# GECBalloonMCUFlightBoard_REV2_0_5-6-19.net
KiCad netlist of a schematic drawn in EAGLE
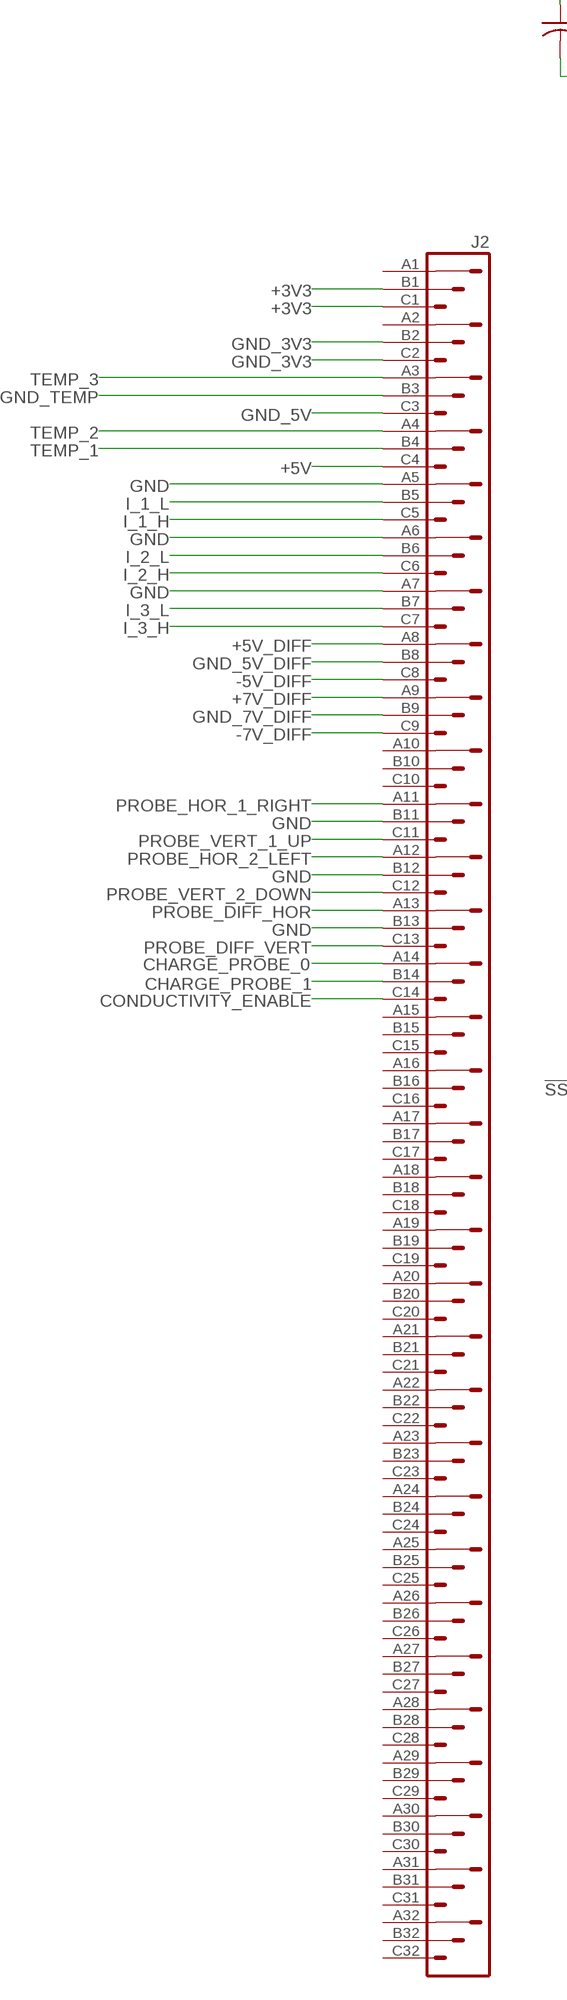
[diagram p0: schematic, sheet 1, part 1 of 2]
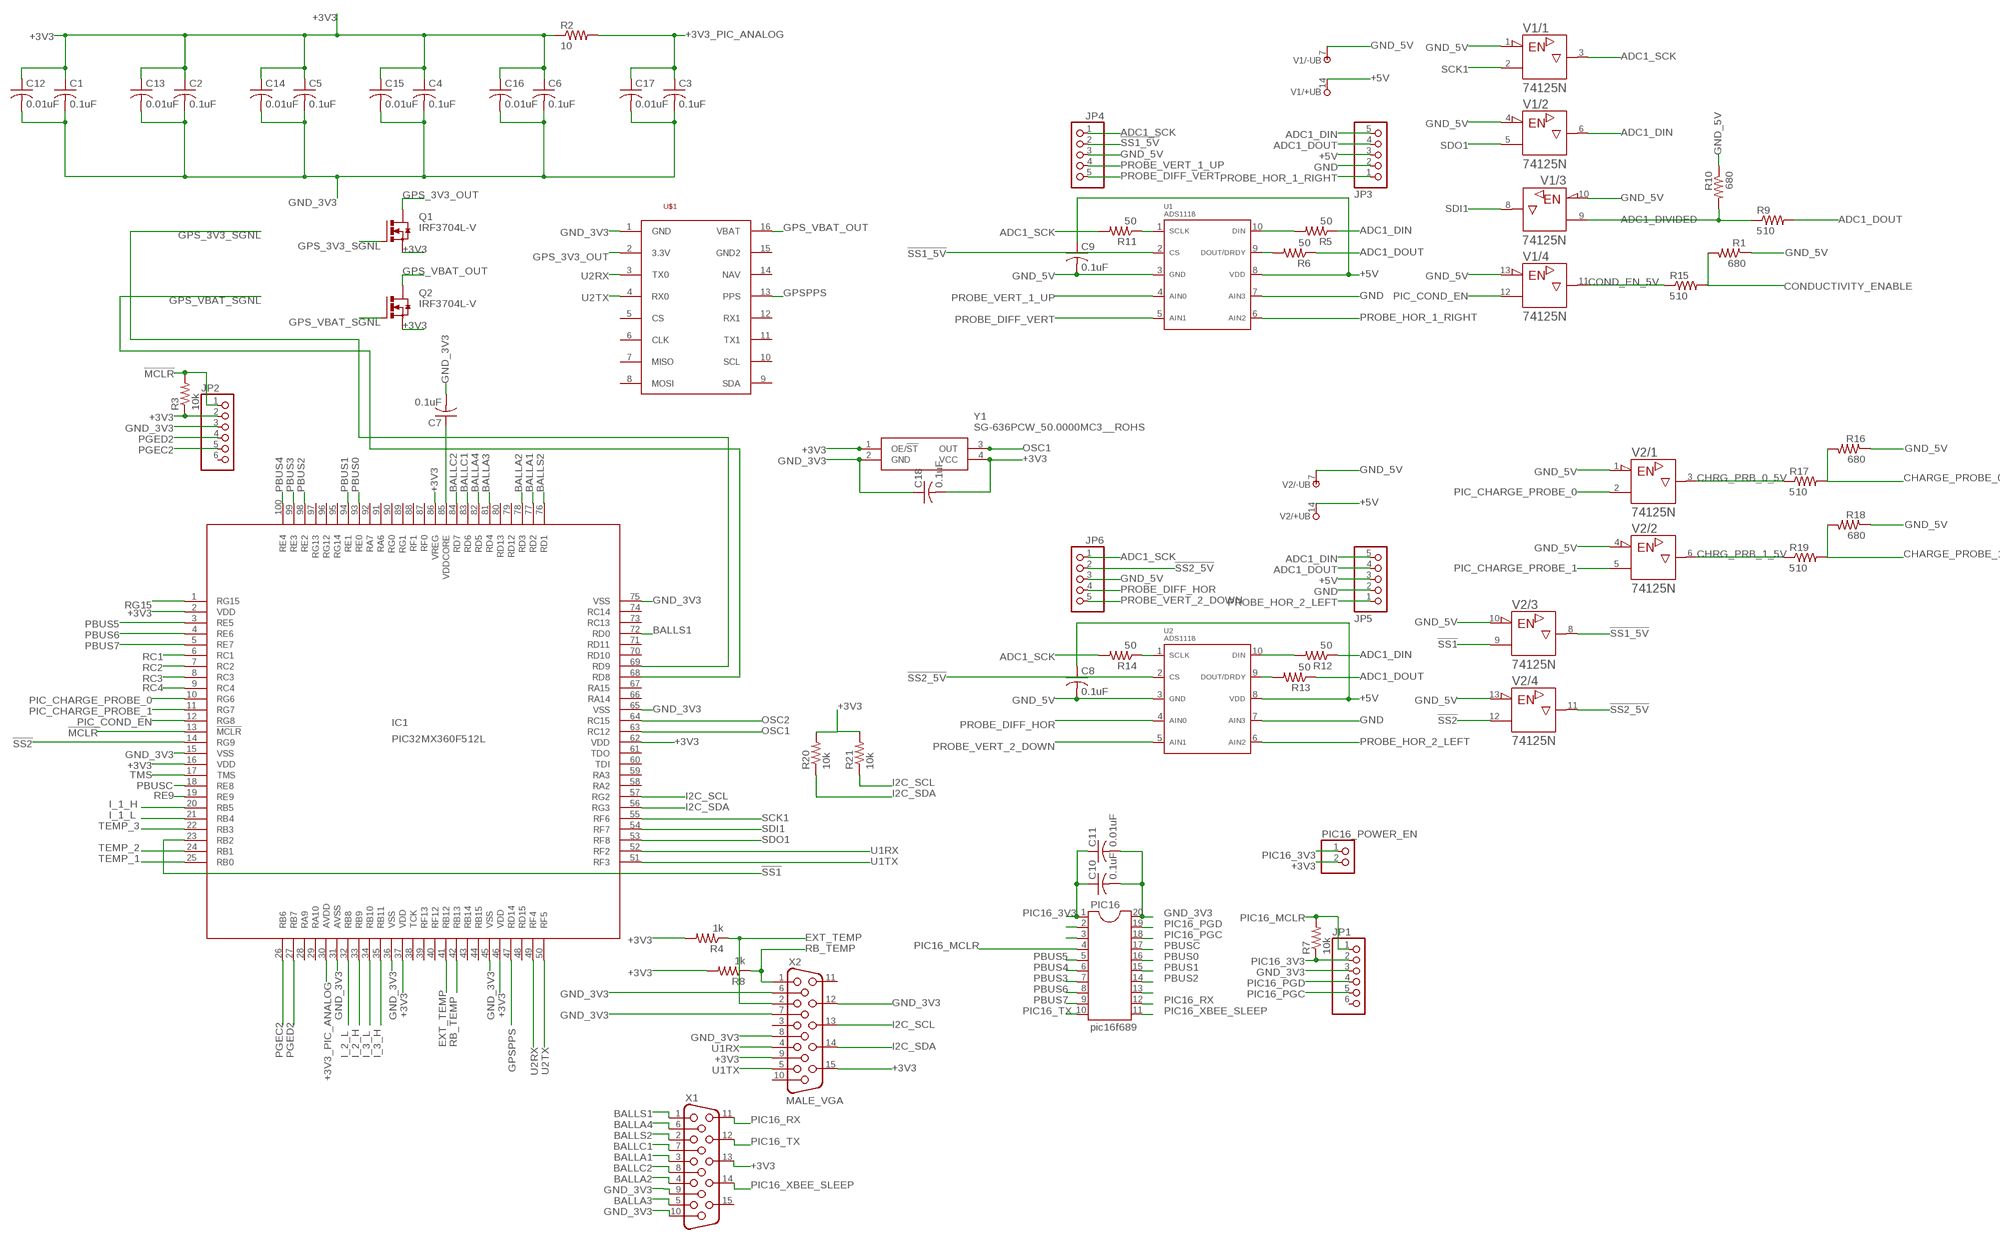
[diagram p1: schematic, sheet 1, part 2 of 2]

(export (version "E")
  (design (tool "Eeschema 10.0.6"))
  (components
    (comp (ref "C1")
      (value "0.1uF")
      (footprint "eagle-import:C1206")
      (libsource (lib "eagle-import") (part "C-USC1206"))
    )
    (comp (ref "C2")
      (value "0.1uF")
      (footprint "eagle-import:C1206")
      (libsource (lib "eagle-import") (part "C-USC1206"))
    )
    (comp (ref "C3")
      (value "0.1uF")
      (footprint "eagle-import:C1206")
      (libsource (lib "eagle-import") (part "C-USC1206"))
    )
    (comp (ref "C4")
      (value "0.1uF")
      (footprint "eagle-import:C1206")
      (libsource (lib "eagle-import") (part "C-USC1206"))
    )
    (comp (ref "C5")
      (value "0.1uF")
      (footprint "eagle-import:C1206")
      (libsource (lib "eagle-import") (part "C-USC1206"))
    )
    (comp (ref "C6")
      (value "0.1uF")
      (footprint "eagle-import:C1206")
      (libsource (lib "eagle-import") (part "C-USC1206"))
    )
    (comp (ref "C7")
      (value "0.1uF")
      (footprint "eagle-import:C1206")
      (libsource (lib "eagle-import") (part "C-USC1206"))
    )
    (comp (ref "C8")
      (value "0.1uF")
      (footprint "eagle-import:C1206")
      (libsource (lib "eagle-import") (part "C-USC1206"))
    )
    (comp (ref "C9")
      (value "0.1uF")
      (footprint "eagle-import:C1206")
      (libsource (lib "eagle-import") (part "C-USC1206"))
    )
    (comp (ref "C10")
      (value "0.1uF")
      (footprint "eagle-import:C1206")
      (libsource (lib "eagle-import") (part "C-USC1206"))
    )
    (comp (ref "C11")
      (value "0.01uF")
      (footprint "eagle-import:C1206")
      (libsource (lib "eagle-import") (part "C-USC1206"))
    )
    (comp (ref "C12")
      (value "0.01uF")
      (footprint "eagle-import:C1206")
      (libsource (lib "eagle-import") (part "C-USC1206"))
    )
    (comp (ref "C13")
      (value "0.01uF")
      (footprint "eagle-import:C1206")
      (libsource (lib "eagle-import") (part "C-USC1206"))
    )
    (comp (ref "C14")
      (value "0.01uF")
      (footprint "eagle-import:C1206")
      (libsource (lib "eagle-import") (part "C-USC1206"))
    )
    (comp (ref "C15")
      (value "0.01uF")
      (footprint "eagle-import:C1206")
      (libsource (lib "eagle-import") (part "C-USC1206"))
    )
    (comp (ref "C16")
      (value "0.01uF")
      (footprint "eagle-import:C1206")
      (libsource (lib "eagle-import") (part "C-USC1206"))
    )
    (comp (ref "C17")
      (value "0.01uF")
      (footprint "eagle-import:C1206")
      (libsource (lib "eagle-import") (part "C-USC1206"))
    )
    (comp (ref "C18")
      (value "0.1uF")
      (footprint "eagle-import:C1206")
      (libsource (lib "eagle-import") (part "C-USC1206"))
    )
    (comp (ref "IC1")
      (value "PIC32MX360F512L")
      (footprint "eagle-import:TQFP100")
      (libsource (lib "eagle-import") (part "PIC32MX360F512L"))
    )
    (comp (ref "J2")
      (value "VG96KB")
      (footprint "eagle-import:VG96KB")
      (libsource (lib "eagle-import") (part "VG96KB"))
    )
    (comp (ref "JP1")
      (value "PINHD-1X6")
      (footprint "eagle-import:1X06")
      (libsource (lib "eagle-import") (part "PINHD-1X6"))
    )
    (comp (ref "JP2")
      (value "PINHD-1X6")
      (footprint "eagle-import:1X06")
      (libsource (lib "eagle-import") (part "PINHD-1X6"))
    )
    (comp (ref "JP3")
      (value "PINHD-1X5")
      (footprint "eagle-import:1X05")
      (libsource (lib "eagle-import") (part "PINHD-1X5"))
    )
    (comp (ref "JP4")
      (value "PINHD-1X5")
      (footprint "eagle-import:1X05")
      (libsource (lib "eagle-import") (part "PINHD-1X5"))
    )
    (comp (ref "JP5")
      (value "PINHD-1X5")
      (footprint "eagle-import:1X05")
      (libsource (lib "eagle-import") (part "PINHD-1X5"))
    )
    (comp (ref "JP6")
      (value "PINHD-1X5")
      (footprint "eagle-import:1X05")
      (libsource (lib "eagle-import") (part "PINHD-1X5"))
    )
    (comp (ref "PIC16")
      (value "pic16f689")
      (footprint "eagle-import:DIL20")
      (libsource (lib "eagle-import") (part "DIL20"))
    )
    (comp (ref "PIC16_POWER_EN")
      (value "PINHD-1X2")
      (footprint "eagle-import:1X02")
      (libsource (lib "eagle-import") (part "PINHD-1X2"))
    )
    (comp (ref "Q1")
      (value "IRF3704L-V")
      (footprint "eagle-import:TO262-V")
      (libsource (lib "eagle-import") (part "IRF3704L-V"))
    )
    (comp (ref "Q2")
      (value "IRF3704L-V")
      (footprint "eagle-import:TO262-V")
      (libsource (lib "eagle-import") (part "IRF3704L-V"))
    )
    (comp (ref "R1")
      (value "680")
      (footprint "eagle-import:R1206")
      (libsource (lib "eagle-import") (part "resistor_R-US_R1206"))
    )
    (comp (ref "R2")
      (value "10")
      (footprint "eagle-import:M1206")
      (libsource (lib "eagle-import") (part "R-US_M1206"))
    )
    (comp (ref "R3")
      (value "10k")
      (footprint "eagle-import:M1206")
      (libsource (lib "eagle-import") (part "R-US_M1206"))
    )
    (comp (ref "R4")
      (value "1k")
      (footprint "eagle-import:0414_15")
      (libsource (lib "eagle-import") (part "resistor_R-US_0414/15"))
    )
    (comp (ref "R5")
      (value "50")
      (footprint "eagle-import:M1206")
      (libsource (lib "eagle-import") (part "R-US_M1206"))
    )
    (comp (ref "R6")
      (value "50")
      (footprint "eagle-import:M1206")
      (libsource (lib "eagle-import") (part "R-US_M1206"))
    )
    (comp (ref "R7")
      (value "10k")
      (footprint "eagle-import:M1206")
      (libsource (lib "eagle-import") (part "R-US_M1206"))
    )
    (comp (ref "R8")
      (value "1k")
      (footprint "eagle-import:0414_15")
      (libsource (lib "eagle-import") (part "resistor_R-US_0414/15"))
    )
    (comp (ref "R9")
      (value "510")
      (footprint "eagle-import:R1206")
      (libsource (lib "eagle-import") (part "resistor_R-US_R1206"))
    )
    (comp (ref "R10")
      (value "680")
      (footprint "eagle-import:R1206")
      (libsource (lib "eagle-import") (part "resistor_R-US_R1206"))
    )
    (comp (ref "R11")
      (value "50")
      (footprint "eagle-import:M1206")
      (libsource (lib "eagle-import") (part "R-US_M1206"))
    )
    (comp (ref "R12")
      (value "50")
      (footprint "eagle-import:M1206")
      (libsource (lib "eagle-import") (part "R-US_M1206"))
    )
    (comp (ref "R13")
      (value "50")
      (footprint "eagle-import:M1206")
      (libsource (lib "eagle-import") (part "R-US_M1206"))
    )
    (comp (ref "R14")
      (value "50")
      (footprint "eagle-import:M1206")
      (libsource (lib "eagle-import") (part "R-US_M1206"))
    )
    (comp (ref "R15")
      (value "510")
      (footprint "eagle-import:R1206")
      (libsource (lib "eagle-import") (part "resistor_R-US_R1206"))
    )
    (comp (ref "R16")
      (value "680")
      (footprint "eagle-import:R1206")
      (libsource (lib "eagle-import") (part "resistor_R-US_R1206"))
    )
    (comp (ref "R17")
      (value "510")
      (footprint "eagle-import:R1206")
      (libsource (lib "eagle-import") (part "resistor_R-US_R1206"))
    )
    (comp (ref "R18")
      (value "680")
      (footprint "eagle-import:R1206")
      (libsource (lib "eagle-import") (part "resistor_R-US_R1206"))
    )
    (comp (ref "R19")
      (value "510")
      (footprint "eagle-import:R1206")
      (libsource (lib "eagle-import") (part "resistor_R-US_R1206"))
    )
    (comp (ref "R20")
      (value "10k")
      (footprint "eagle-import:M1206")
      (libsource (lib "eagle-import") (part "R-US_M1206"))
    )
    (comp (ref "R21")
      (value "10k")
      (footprint "eagle-import:M1206")
      (libsource (lib "eagle-import") (part "R-US_M1206"))
    )
    (comp (ref "U$1")
      (value "SPARKFUN_VENUS_GPS_BREAKOUT")
      (footprint "eagle-import:SPARKFUN_BOARD")
      (libsource (lib "eagle-import") (part "SPARKFUN_VENUS_GPS_BREAKOUT"))
    )
    (comp (ref "U1")
      (value "ADS1118")
      (footprint "eagle-import:MSOP10")
      (libsource (lib "eagle-import") (part "ADS1118_MSOP10"))
    )
    (comp (ref "U2")
      (value "ADS1118")
      (footprint "eagle-import:MSOP10")
      (libsource (lib "eagle-import") (part "ADS1118_MSOP10"))
    )
    (comp (ref "V1")
      (value "74125N")
      (footprint "eagle-import:DIL14")
      (libsource (lib "eagle-import") (part "74125N"))
    )
    (comp (ref "V2")
      (value "74125N")
      (footprint "eagle-import:DIL14")
      (libsource (lib "eagle-import") (part "74125N"))
    )
    (comp (ref "X1")
      (value "HF15H")
      (footprint "eagle-import:HDF15H")
      (libsource (lib "eagle-import") (part "HF15H"))
    )
    (comp (ref "X2")
      (value "MALE_VGA")
      (footprint "eagle-import:MALE_PACKAGE")
      (libsource (lib "eagle-import") (part "MALE_VGA"))
    )
    (comp (ref "Y1")
      (value "SG-636PCW_50.0000MC3__ROHS")
      (footprint "eagle-import:SG-636")
      (fields (field (name "ARROW_PART_NUMBER") "SG-636PCW 50.0000MC3: ROHS"))
      (libsource (lib "eagle-import") (part "SG-636PCW_50.0000MC3__ROHS"))
    )
  )
  (nets
    (net (code "1") (name "/+3V3") (class "Default")
      (node (ref "C1") (pin "1") (pinfunction "1_1") (pintype "passive"))
      (node (ref "C12") (pin "1") (pinfunction "1_1") (pintype "passive"))
      (node (ref "C13") (pin "1") (pinfunction "1_1") (pintype "passive"))
      (node (ref "C14") (pin "1") (pinfunction "1_1") (pintype "passive"))
      (node (ref "C15") (pin "1") (pinfunction "1_1") (pintype "passive"))
      (node (ref "C16") (pin "1") (pinfunction "1_1") (pintype "passive"))
      (node (ref "C18") (pin "2") (pinfunction "2_2") (pintype "passive"))
      (node (ref "C2") (pin "1") (pinfunction "1_1") (pintype "passive"))
      (node (ref "C4") (pin "1") (pinfunction "1_1") (pintype "passive"))
      (node (ref "C5") (pin "1") (pinfunction "1_1") (pintype "passive"))
      (node (ref "C6") (pin "1") (pinfunction "1_1") (pintype "passive"))
      (node (ref "IC1") (pin "16") (pinfunction "VDD_16") (pintype "power_in"))
      (node (ref "IC1") (pin "2") (pinfunction "VDD_2") (pintype "power_in"))
      (node (ref "IC1") (pin "37") (pinfunction "VDD_37") (pintype "power_in"))
      (node (ref "IC1") (pin "46") (pinfunction "VDD_46") (pintype "power_in"))
      (node (ref "IC1") (pin "62") (pinfunction "VDD_62") (pintype "power_in"))
      (node (ref "IC1") (pin "86") (pinfunction "VREG_86") (pintype "passive"))
      (node (ref "J2") (pin "B1") (pinfunction "B1_B1") (pintype "passive"))
      (node (ref "J2") (pin "C1") (pinfunction "C1_C1") (pintype "passive"))
      (node (ref "JP2") (pin "2") (pinfunction "2_2") (pintype "passive"))
      (node (ref "PIC16_POWER_EN") (pin "2") (pinfunction "2_2") (pintype "passive"))
      (node (ref "Q1") (pin "3") (pinfunction "S_3") (pintype "passive"))
      (node (ref "Q2") (pin "3") (pinfunction "S_3") (pintype "passive"))
      (node (ref "R2") (pin "1") (pinfunction "1_1") (pintype "passive"))
      (node (ref "R20") (pin "2") (pinfunction "2_2") (pintype "passive"))
      (node (ref "R21") (pin "2") (pinfunction "2_2") (pintype "passive"))
      (node (ref "R3") (pin "1") (pinfunction "1_1") (pintype "passive"))
      (node (ref "R4") (pin "2") (pinfunction "2_2") (pintype "passive"))
      (node (ref "R8") (pin "2") (pinfunction "2_2") (pintype "passive"))
      (node (ref "X1") (pin "13") (pinfunction "13_13") (pintype "passive"))
      (node (ref "X2") (pin "15") (pinfunction "15_15") (pintype "passive"))
      (node (ref "X2") (pin "9") (pinfunction "9_9") (pintype "passive"))
      (node (ref "Y1") (pin "1") (pinfunction "OE/~{ST}_1") (pintype "input"))
      (node (ref "Y1") (pin "4") (pinfunction "VCC_4") (pintype "power_in"))
    )
    (net (code "2") (name "/+3V3_PIC_ANALOG") (class "Default")
      (node (ref "C17") (pin "1") (pinfunction "1_1") (pintype "passive"))
      (node (ref "C3") (pin "1") (pinfunction "1_1") (pintype "passive"))
      (node (ref "IC1") (pin "30") (pinfunction "AVDD_30") (pintype "power_in"))
      (node (ref "R2") (pin "2") (pinfunction "2_2") (pintype "passive"))
    )
    (net (code "3") (name "/+5V") (class "Default")
      (node (ref "C8") (pin "1") (pinfunction "1_1") (pintype "passive"))
      (node (ref "C9") (pin "1") (pinfunction "1_1") (pintype "passive"))
      (node (ref "J2") (pin "C4") (pinfunction "C4_C4") (pintype "passive"))
      (node (ref "JP3") (pin "3") (pinfunction "3_3") (pintype "passive"))
      (node (ref "JP5") (pin "3") (pinfunction "3_3") (pintype "passive"))
      (node (ref "U1") (pin "8") (pinfunction "VDD_8") (pintype "bidirectional"))
      (node (ref "U2") (pin "8") (pinfunction "VDD_8") (pintype "bidirectional"))
      (node (ref "V1") (pin "14") (pinfunction "+UB_14") (pintype "power_in"))
      (node (ref "V2") (pin "14") (pinfunction "+UB_14") (pintype "power_in"))
    )
    (net (code "4") (name "/+5V_DIFF") (class "Default")
      (node (ref "J2") (pin "A8") (pinfunction "A8_A8") (pintype "passive"))
    )
    (net (code "5") (name "/+7V_DIFF") (class "Default")
      (node (ref "J2") (pin "A9") (pinfunction "A9_A9") (pintype "passive"))
    )
    (net (code "6") (name "/-5V_DIFF") (class "Default")
      (node (ref "J2") (pin "C8") (pinfunction "C8_C8") (pintype "passive"))
    )
    (net (code "7") (name "/-7V_DIFF") (class "Default")
      (node (ref "J2") (pin "C9") (pinfunction "C9_C9") (pintype "passive"))
    )
    (net (code "8") (name "/ADC1_DIN") (class "Default")
      (node (ref "JP3") (pin "5") (pinfunction "5_5") (pintype "passive"))
      (node (ref "JP5") (pin "5") (pinfunction "5_5") (pintype "passive"))
      (node (ref "R12") (pin "1") (pinfunction "1_1") (pintype "passive"))
      (node (ref "R5") (pin "1") (pinfunction "1_1") (pintype "passive"))
      (node (ref "V1") (pin "6") (pinfunction "Y_6") (pintype "tri_state"))
    )
    (net (code "9") (name "/ADC1_DIVIDED") (class "Default")
      (node (ref "R10") (pin "2") (pinfunction "2_2") (pintype "passive"))
      (node (ref "R9") (pin "1") (pinfunction "1_1") (pintype "passive"))
      (node (ref "V1") (pin "9") (pinfunction "A_9") (pintype "input"))
    )
    (net (code "10") (name "/ADC1_DOUT") (class "Default")
      (node (ref "JP3") (pin "4") (pinfunction "4_4") (pintype "passive"))
      (node (ref "JP5") (pin "4") (pinfunction "4_4") (pintype "passive"))
      (node (ref "R13") (pin "1") (pinfunction "1_1") (pintype "passive"))
      (node (ref "R6") (pin "1") (pinfunction "1_1") (pintype "passive"))
      (node (ref "R9") (pin "2") (pinfunction "2_2") (pintype "passive"))
    )
    (net (code "11") (name "/ADC1_SCK") (class "Default")
      (node (ref "JP4") (pin "1") (pinfunction "1_1") (pintype "passive"))
      (node (ref "JP6") (pin "1") (pinfunction "1_1") (pintype "passive"))
      (node (ref "R11") (pin "2") (pinfunction "2_2") (pintype "passive"))
      (node (ref "R14") (pin "2") (pinfunction "2_2") (pintype "passive"))
      (node (ref "V1") (pin "3") (pinfunction "Y_3") (pintype "tri_state"))
    )
    (net (code "12") (name "/BALLA1") (class "Default")
      (node (ref "IC1") (pin "77") (pinfunction "RD2_77") (pintype "bidirectional"))
      (node (ref "X1") (pin "3") (pinfunction "3_3") (pintype "passive"))
    )
    (net (code "13") (name "/BALLA2") (class "Default")
      (node (ref "IC1") (pin "78") (pinfunction "RD3_78") (pintype "bidirectional"))
      (node (ref "X1") (pin "4") (pinfunction "4_4") (pintype "passive"))
    )
    (net (code "14") (name "/BALLA3") (class "Default")
      (node (ref "IC1") (pin "81") (pinfunction "RD4_81") (pintype "bidirectional"))
      (node (ref "X1") (pin "5") (pinfunction "5_5") (pintype "passive"))
    )
    (net (code "15") (name "/BALLA4") (class "Default")
      (node (ref "IC1") (pin "82") (pinfunction "RD5_82") (pintype "bidirectional"))
      (node (ref "X1") (pin "6") (pinfunction "6_6") (pintype "passive"))
    )
    (net (code "16") (name "/BALLC1") (class "Default")
      (node (ref "IC1") (pin "83") (pinfunction "RD6_83") (pintype "bidirectional"))
      (node (ref "X1") (pin "7") (pinfunction "7_7") (pintype "passive"))
    )
    (net (code "17") (name "/BALLC2") (class "Default")
      (node (ref "IC1") (pin "84") (pinfunction "RD7_84") (pintype "bidirectional"))
      (node (ref "X1") (pin "8") (pinfunction "8_8") (pintype "passive"))
    )
    (net (code "18") (name "/BALLS1") (class "Default")
      (node (ref "IC1") (pin "72") (pinfunction "RD0_72") (pintype "bidirectional"))
      (node (ref "X1") (pin "1") (pinfunction "1_1") (pintype "passive"))
    )
    (net (code "19") (name "/BALLS2") (class "Default")
      (node (ref "IC1") (pin "76") (pinfunction "RD1_76") (pintype "bidirectional"))
      (node (ref "X1") (pin "2") (pinfunction "2_2") (pintype "passive"))
    )
    (net (code "20") (name "/CHARGE_PROBE_0") (class "Default")
      (node (ref "J2") (pin "A14") (pinfunction "A14_A14") (pintype "passive"))
      (node (ref "R16") (pin "2") (pinfunction "2_2") (pintype "passive"))
      (node (ref "R17") (pin "2") (pinfunction "2_2") (pintype "passive"))
    )
    (net (code "21") (name "/CHARGE_PROBE_1") (class "Default")
      (node (ref "J2") (pin "B14") (pinfunction "B14_B14") (pintype "passive"))
      (node (ref "R18") (pin "2") (pinfunction "2_2") (pintype "passive"))
      (node (ref "R19") (pin "2") (pinfunction "2_2") (pintype "passive"))
    )
    (net (code "22") (name "/CHRG_PRB_0_5V") (class "Default")
      (node (ref "R17") (pin "1") (pinfunction "1_1") (pintype "passive"))
      (node (ref "V2") (pin "3") (pinfunction "Y_3") (pintype "tri_state"))
    )
    (net (code "23") (name "/CHRG_PRB_1_5V") (class "Default")
      (node (ref "R19") (pin "1") (pinfunction "1_1") (pintype "passive"))
      (node (ref "V2") (pin "6") (pinfunction "Y_6") (pintype "tri_state"))
    )
    (net (code "24") (name "/CONDUCTIVITY_ENABLE") (class "Default")
      (node (ref "J2") (pin "C14") (pinfunction "C14_C14") (pintype "passive"))
      (node (ref "R1") (pin "2") (pinfunction "2_2") (pintype "passive"))
      (node (ref "R15") (pin "2") (pinfunction "2_2") (pintype "passive"))
    )
    (net (code "25") (name "/COND_EN_5V") (class "Default")
      (node (ref "R15") (pin "1") (pinfunction "1_1") (pintype "passive"))
      (node (ref "V1") (pin "11") (pinfunction "Y_11") (pintype "tri_state"))
    )
    (net (code "26") (name "/EXT_TEMP") (class "Default")
      (node (ref "IC1") (pin "41") (pinfunction "RB12_41") (pintype "bidirectional"))
      (node (ref "R4") (pin "1") (pinfunction "1_1") (pintype "passive"))
      (node (ref "X2") (pin "2") (pinfunction "2_2") (pintype "passive"))
    )
    (net (code "27") (name "/GND") (class "Default")
      (node (ref "J2") (pin "A5") (pinfunction "A5_A5") (pintype "passive"))
      (node (ref "J2") (pin "A6") (pinfunction "A6_A6") (pintype "passive"))
      (node (ref "J2") (pin "A7") (pinfunction "A7_A7") (pintype "passive"))
      (node (ref "J2") (pin "B11") (pinfunction "B11_B11") (pintype "passive"))
      (node (ref "J2") (pin "B12") (pinfunction "B12_B12") (pintype "passive"))
      (node (ref "J2") (pin "B13") (pinfunction "B13_B13") (pintype "passive"))
      (node (ref "JP3") (pin "2") (pinfunction "2_2") (pintype "passive"))
      (node (ref "JP5") (pin "2") (pinfunction "2_2") (pintype "passive"))
      (node (ref "U1") (pin "7") (pinfunction "AIN3_7") (pintype "bidirectional"))
      (node (ref "U2") (pin "7") (pinfunction "AIN3_7") (pintype "bidirectional"))
    )
    (net (code "28") (name "/GND_3V3") (class "Default")
      (node (ref "C1") (pin "2") (pinfunction "2_2") (pintype "passive"))
      (node (ref "C10") (pin "2") (pinfunction "2_2") (pintype "passive"))
      (node (ref "C11") (pin "2") (pinfunction "2_2") (pintype "passive"))
      (node (ref "C12") (pin "2") (pinfunction "2_2") (pintype "passive"))
      (node (ref "C13") (pin "2") (pinfunction "2_2") (pintype "passive"))
      (node (ref "C14") (pin "2") (pinfunction "2_2") (pintype "passive"))
      (node (ref "C15") (pin "2") (pinfunction "2_2") (pintype "passive"))
      (node (ref "C16") (pin "2") (pinfunction "2_2") (pintype "passive"))
      (node (ref "C17") (pin "2") (pinfunction "2_2") (pintype "passive"))
      (node (ref "C18") (pin "1") (pinfunction "1_1") (pintype "passive"))
      (node (ref "C2") (pin "2") (pinfunction "2_2") (pintype "passive"))
      (node (ref "C3") (pin "2") (pinfunction "2_2") (pintype "passive"))
      (node (ref "C4") (pin "2") (pinfunction "2_2") (pintype "passive"))
      (node (ref "C5") (pin "2") (pinfunction "2_2") (pintype "passive"))
      (node (ref "C6") (pin "2") (pinfunction "2_2") (pintype "passive"))
      (node (ref "C7") (pin "2") (pinfunction "2_2") (pintype "passive"))
      (node (ref "IC1") (pin "15") (pinfunction "VSS_15") (pintype "power_in"))
      (node (ref "IC1") (pin "31") (pinfunction "AVSS_31") (pintype "power_in"))
      (node (ref "IC1") (pin "36") (pinfunction "VSS_36") (pintype "power_in"))
      (node (ref "IC1") (pin "45") (pinfunction "VSS_45") (pintype "power_in"))
      (node (ref "IC1") (pin "65") (pinfunction "VSS_65") (pintype "power_in"))
      (node (ref "IC1") (pin "75") (pinfunction "VSS_75") (pintype "power_in"))
      (node (ref "J2") (pin "B2") (pinfunction "B2_B2") (pintype "passive"))
      (node (ref "J2") (pin "C2") (pinfunction "C2_C2") (pintype "passive"))
      (node (ref "JP1") (pin "3") (pinfunction "3_3") (pintype "passive"))
      (node (ref "JP2") (pin "3") (pinfunction "3_3") (pintype "passive"))
      (node (ref "PIC16") (pin "20") (pinfunction "20_20") (pintype "passive"))
      (node (ref "U$1") (pin "1") (pinfunction "GND_1") (pintype "bidirectional"))
      (node (ref "X1") (pin "10") (pinfunction "10_10") (pintype "passive"))
      (node (ref "X1") (pin "9") (pinfunction "9_9") (pintype "passive"))
      (node (ref "X2") (pin "12") (pinfunction "12_12") (pintype "passive"))
      (node (ref "X2") (pin "6") (pinfunction "6_6") (pintype "passive"))
      (node (ref "X2") (pin "7") (pinfunction "7_7") (pintype "passive"))
      (node (ref "X2") (pin "8") (pinfunction "8_8") (pintype "passive"))
      (node (ref "Y1") (pin "2") (pinfunction "GND_2") (pintype "power_in"))
    )
    (net (code "29") (name "/GND_5V") (class "Default")
      (node (ref "C8") (pin "2") (pinfunction "2_2") (pintype "passive"))
      (node (ref "C9") (pin "2") (pinfunction "2_2") (pintype "passive"))
      (node (ref "J2") (pin "C3") (pinfunction "C3_C3") (pintype "passive"))
      (node (ref "JP4") (pin "3") (pinfunction "3_3") (pintype "passive"))
      (node (ref "JP6") (pin "3") (pinfunction "3_3") (pintype "passive"))
      (node (ref "R1") (pin "1") (pinfunction "1_1") (pintype "passive"))
      (node (ref "R10") (pin "1") (pinfunction "1_1") (pintype "passive"))
      (node (ref "R16") (pin "1") (pinfunction "1_1") (pintype "passive"))
      (node (ref "R18") (pin "1") (pinfunction "1_1") (pintype "passive"))
      (node (ref "U1") (pin "3") (pinfunction "GND_3") (pintype "bidirectional"))
      (node (ref "U2") (pin "3") (pinfunction "GND_3") (pintype "bidirectional"))
      (node (ref "V1") (pin "1") (pinfunction "~{G}_1") (pintype "input"))
      (node (ref "V1") (pin "10") (pinfunction "~{G}_10") (pintype "input"))
      (node (ref "V1") (pin "13") (pinfunction "~{G}_13") (pintype "input"))
      (node (ref "V1") (pin "4") (pinfunction "~{G}_4") (pintype "input"))
      (node (ref "V1") (pin "7") (pinfunction "-UB_7") (pintype "power_in"))
      (node (ref "V2") (pin "1") (pinfunction "~{G}_1") (pintype "input"))
      (node (ref "V2") (pin "10") (pinfunction "~{G}_10") (pintype "input"))
      (node (ref "V2") (pin "13") (pinfunction "~{G}_13") (pintype "input"))
      (node (ref "V2") (pin "4") (pinfunction "~{G}_4") (pintype "input"))
      (node (ref "V2") (pin "7") (pinfunction "-UB_7") (pintype "power_in"))
    )
    (net (code "30") (name "/GND_5V_DIFF") (class "Default")
      (node (ref "J2") (pin "B8") (pinfunction "B8_B8") (pintype "passive"))
    )
    (net (code "31") (name "/GND_7V_DIFF") (class "Default")
      (node (ref "J2") (pin "B9") (pinfunction "B9_B9") (pintype "passive"))
    )
    (net (code "32") (name "/GND_TEMP") (class "Default")
      (node (ref "J2") (pin "B3") (pinfunction "B3_B3") (pintype "passive"))
    )
    (net (code "33") (name "/GPSPPS") (class "Default")
      (node (ref "IC1") (pin "47") (pinfunction "RD14_47") (pintype "bidirectional"))
      (node (ref "U$1") (pin "13") (pinfunction "PPS_13") (pintype "bidirectional"))
    )
    (net (code "34") (name "/GPS_3V3_OUT") (class "Default")
      (node (ref "Q1") (pin "2") (pinfunction "D_2") (pintype "passive"))
      (node (ref "U$1") (pin "2") (pinfunction "3.3V_2") (pintype "bidirectional"))
    )
    (net (code "35") (name "/GPS_3V3_SGNL") (class "Default")
      (node (ref "IC1") (pin "69") (pinfunction "RD9_69") (pintype "bidirectional"))
      (node (ref "Q1") (pin "1") (pinfunction "G_1") (pintype "passive"))
    )
    (net (code "36") (name "/GPS_VBAT_OUT") (class "Default")
      (node (ref "Q2") (pin "2") (pinfunction "D_2") (pintype "passive"))
      (node (ref "U$1") (pin "16") (pinfunction "VBAT_16") (pintype "bidirectional"))
    )
    (net (code "37") (name "/GPS_VBAT_SGNL") (class "Default")
      (node (ref "IC1") (pin "68") (pinfunction "RD8_68") (pintype "bidirectional"))
      (node (ref "Q2") (pin "1") (pinfunction "G_1") (pintype "passive"))
    )
    (net (code "38") (name "/I2C_SCL") (class "Default")
      (node (ref "IC1") (pin "57") (pinfunction "RG2_57") (pintype "bidirectional"))
      (node (ref "R21") (pin "1") (pinfunction "1_1") (pintype "passive"))
      (node (ref "X2") (pin "13") (pinfunction "13_13") (pintype "passive"))
    )
    (net (code "39") (name "/I2C_SDA") (class "Default")
      (node (ref "IC1") (pin "56") (pinfunction "RG3_56") (pintype "bidirectional"))
      (node (ref "R20") (pin "1") (pinfunction "1_1") (pintype "passive"))
      (node (ref "X2") (pin "14") (pinfunction "14_14") (pintype "passive"))
    )
    (net (code "40") (name "/I_1_H") (class "Default")
      (node (ref "IC1") (pin "20") (pinfunction "RB5_20") (pintype "bidirectional"))
      (node (ref "J2") (pin "C5") (pinfunction "C5_C5") (pintype "passive"))
    )
    (net (code "41") (name "/I_1_L") (class "Default")
      (node (ref "IC1") (pin "21") (pinfunction "RB4_21") (pintype "bidirectional"))
      (node (ref "J2") (pin "B5") (pinfunction "B5_B5") (pintype "passive"))
    )
    (net (code "42") (name "/I_2_H") (class "Default")
      (node (ref "IC1") (pin "33") (pinfunction "RB9_33") (pintype "bidirectional"))
      (node (ref "J2") (pin "C6") (pinfunction "C6_C6") (pintype "passive"))
    )
    (net (code "43") (name "/I_2_L") (class "Default")
      (node (ref "IC1") (pin "32") (pinfunction "RB8_32") (pintype "bidirectional"))
      (node (ref "J2") (pin "B6") (pinfunction "B6_B6") (pintype "passive"))
    )
    (net (code "44") (name "/I_3_H") (class "Default")
      (node (ref "IC1") (pin "35") (pinfunction "RB11_35") (pintype "bidirectional"))
      (node (ref "J2") (pin "C7") (pinfunction "C7_C7") (pintype "passive"))
    )
    (net (code "45") (name "/I_3_L") (class "Default")
      (node (ref "IC1") (pin "34") (pinfunction "RB10_34") (pintype "bidirectional"))
      (node (ref "J2") (pin "B7") (pinfunction "B7_B7") (pintype "passive"))
    )
    (net (code "46") (name "/OSC1") (class "Default")
      (node (ref "IC1") (pin "63") (pinfunction "RC12_63") (pintype "bidirectional"))
      (node (ref "Y1") (pin "3") (pinfunction "OUT_3") (pintype "output"))
    )
    (net (code "47") (name "/OSC2") (class "Default")
      (node (ref "IC1") (pin "64") (pinfunction "RC15_64") (pintype "bidirectional"))
    )
    (net (code "48") (name "/PBUS0") (class "Default")
      (node (ref "IC1") (pin "93") (pinfunction "RE0_93") (pintype "bidirectional"))
      (node (ref "PIC16") (pin "16") (pinfunction "16_16") (pintype "passive"))
    )
    (net (code "49") (name "/PBUS1") (class "Default")
      (node (ref "IC1") (pin "94") (pinfunction "RE1_94") (pintype "bidirectional"))
      (node (ref "PIC16") (pin "15") (pinfunction "15_15") (pintype "passive"))
    )
    (net (code "50") (name "/PBUS2") (class "Default")
      (node (ref "IC1") (pin "98") (pinfunction "RE2_98") (pintype "bidirectional"))
      (node (ref "PIC16") (pin "14") (pinfunction "14_14") (pintype "passive"))
    )
    (net (code "51") (name "/PBUS3") (class "Default")
      (node (ref "IC1") (pin "99") (pinfunction "RE3_99") (pintype "bidirectional"))
      (node (ref "PIC16") (pin "7") (pinfunction "7_7") (pintype "passive"))
    )
    (net (code "52") (name "/PBUS4") (class "Default")
      (node (ref "IC1") (pin "100") (pinfunction "RE4_100") (pintype "bidirectional"))
      (node (ref "PIC16") (pin "6") (pinfunction "6_6") (pintype "passive"))
    )
    (net (code "53") (name "/PBUS5") (class "Default")
      (node (ref "IC1") (pin "3") (pinfunction "RE5_3") (pintype "bidirectional"))
      (node (ref "PIC16") (pin "5") (pinfunction "5_5") (pintype "passive"))
    )
    (net (code "54") (name "/PBUS6") (class "Default")
      (node (ref "IC1") (pin "4") (pinfunction "RE6_4") (pintype "bidirectional"))
      (node (ref "PIC16") (pin "8") (pinfunction "8_8") (pintype "passive"))
    )
    (net (code "55") (name "/PBUS7") (class "Default")
      (node (ref "IC1") (pin "5") (pinfunction "RE7_5") (pintype "bidirectional"))
      (node (ref "PIC16") (pin "9") (pinfunction "9_9") (pintype "passive"))
    )
    (net (code "56") (name "/PBUSC") (class "Default")
      (node (ref "IC1") (pin "18") (pinfunction "RE8_18") (pintype "bidirectional"))
      (node (ref "PIC16") (pin "17") (pinfunction "17_17") (pintype "passive"))
    )
    (net (code "57") (name "/PGEC2") (class "Default")
      (node (ref "IC1") (pin "26") (pinfunction "RB6_26") (pintype "bidirectional"))
      (node (ref "JP2") (pin "5") (pinfunction "5_5") (pintype "passive"))
    )
    (net (code "58") (name "/PGED2") (class "Default")
      (node (ref "IC1") (pin "27") (pinfunction "RB7_27") (pintype "bidirectional"))
      (node (ref "JP2") (pin "4") (pinfunction "4_4") (pintype "passive"))
    )
    (net (code "59") (name "/PIC16_3V3") (class "Default")
      (node (ref "C10") (pin "1") (pinfunction "1_1") (pintype "passive"))
      (node (ref "C11") (pin "1") (pinfunction "1_1") (pintype "passive"))
      (node (ref "JP1") (pin "2") (pinfunction "2_2") (pintype "passive"))
      (node (ref "PIC16") (pin "1") (pinfunction "1_1") (pintype "passive"))
      (node (ref "PIC16_POWER_EN") (pin "1") (pinfunction "1_1") (pintype "passive"))
      (node (ref "R7") (pin "1") (pinfunction "1_1") (pintype "passive"))
    )
    (net (code "60") (name "/PIC16_MCLR") (class "Default")
      (node (ref "JP1") (pin "1") (pinfunction "1_1") (pintype "passive"))
      (node (ref "PIC16") (pin "4") (pinfunction "4_4") (pintype "passive"))
      (node (ref "R7") (pin "2") (pinfunction "2_2") (pintype "passive"))
    )
    (net (code "61") (name "/PIC16_PGC") (class "Default")
      (node (ref "JP1") (pin "5") (pinfunction "5_5") (pintype "passive"))
      (node (ref "PIC16") (pin "18") (pinfunction "18_18") (pintype "passive"))
    )
    (net (code "62") (name "/PIC16_PGD") (class "Default")
      (node (ref "JP1") (pin "4") (pinfunction "4_4") (pintype "passive"))
      (node (ref "PIC16") (pin "19") (pinfunction "19_19") (pintype "passive"))
    )
    (net (code "63") (name "/PIC16_RX") (class "Default")
      (node (ref "PIC16") (pin "12") (pinfunction "12_12") (pintype "passive"))
      (node (ref "X1") (pin "11") (pinfunction "11_11") (pintype "passive"))
    )
    (net (code "64") (name "/PIC16_TX") (class "Default")
      (node (ref "PIC16") (pin "10") (pinfunction "10_10") (pintype "passive"))
      (node (ref "X1") (pin "12") (pinfunction "12_12") (pintype "passive"))
    )
    (net (code "65") (name "/PIC16_XBEE_SLEEP") (class "Default")
      (node (ref "PIC16") (pin "11") (pinfunction "11_11") (pintype "passive"))
      (node (ref "X1") (pin "14") (pinfunction "14_14") (pintype "passive"))
    )
    (net (code "66") (name "/PIC_CHARGE_PROBE_0") (class "Default")
      (node (ref "IC1") (pin "10") (pinfunction "RG6_10") (pintype "bidirectional"))
      (node (ref "V2") (pin "2") (pinfunction "A_2") (pintype "input"))
    )
    (net (code "67") (name "/PIC_CHARGE_PROBE_1") (class "Default")
      (node (ref "IC1") (pin "11") (pinfunction "RG7_11") (pintype "bidirectional"))
      (node (ref "V2") (pin "5") (pinfunction "A_5") (pintype "input"))
    )
    (net (code "68") (name "/PIC_COND_EN") (class "Default")
      (node (ref "IC1") (pin "12") (pinfunction "RG8_12") (pintype "bidirectional"))
      (node (ref "V1") (pin "12") (pinfunction "A_12") (pintype "input"))
    )
    (net (code "69") (name "/PROBE_DIFF_HOR") (class "Default")
      (node (ref "J2") (pin "A13") (pinfunction "A13_A13") (pintype "passive"))
      (node (ref "JP6") (pin "4") (pinfunction "4_4") (pintype "passive"))
      (node (ref "U2") (pin "4") (pinfunction "AIN0_4") (pintype "bidirectional"))
    )
    (net (code "70") (name "/PROBE_DIFF_VERT") (class "Default")
      (node (ref "J2") (pin "C13") (pinfunction "C13_C13") (pintype "passive"))
      (node (ref "JP4") (pin "5") (pinfunction "5_5") (pintype "passive"))
      (node (ref "U1") (pin "5") (pinfunction "AIN1_5") (pintype "bidirectional"))
    )
    (net (code "71") (name "/PROBE_HOR_1_RIGHT") (class "Default")
      (node (ref "J2") (pin "A11") (pinfunction "A11_A11") (pintype "passive"))
      (node (ref "JP3") (pin "1") (pinfunction "1_1") (pintype "passive"))
      (node (ref "U1") (pin "6") (pinfunction "AIN2_6") (pintype "bidirectional"))
    )
    (net (code "72") (name "/PROBE_HOR_2_LEFT") (class "Default")
      (node (ref "J2") (pin "A12") (pinfunction "A12_A12") (pintype "passive"))
      (node (ref "JP5") (pin "1") (pinfunction "1_1") (pintype "passive"))
      (node (ref "U2") (pin "6") (pinfunction "AIN2_6") (pintype "bidirectional"))
    )
    (net (code "73") (name "/PROBE_VERT_1_UP") (class "Default")
      (node (ref "J2") (pin "C11") (pinfunction "C11_C11") (pintype "passive"))
      (node (ref "JP4") (pin "4") (pinfunction "4_4") (pintype "passive"))
      (node (ref "U1") (pin "4") (pinfunction "AIN0_4") (pintype "bidirectional"))
    )
    (net (code "74") (name "/PROBE_VERT_2_DOWN") (class "Default")
      (node (ref "J2") (pin "C12") (pinfunction "C12_C12") (pintype "passive"))
      (node (ref "JP6") (pin "5") (pinfunction "5_5") (pintype "passive"))
      (node (ref "U2") (pin "5") (pinfunction "AIN1_5") (pintype "bidirectional"))
    )
    (net (code "75") (name "/RB_TEMP") (class "Default")
      (node (ref "IC1") (pin "42") (pinfunction "RB13_42") (pintype "bidirectional"))
      (node (ref "R8") (pin "1") (pinfunction "1_1") (pintype "passive"))
      (node (ref "X2") (pin "1") (pinfunction "1_1") (pintype "passive"))
    )
    (net (code "76") (name "/RC1") (class "Default")
      (node (ref "IC1") (pin "6") (pinfunction "RC1_6") (pintype "bidirectional"))
    )
    (net (code "77") (name "/RC2") (class "Default")
      (node (ref "IC1") (pin "7") (pinfunction "RC2_7") (pintype "bidirectional"))
    )
    (net (code "78") (name "/RC3") (class "Default")
      (node (ref "IC1") (pin "8") (pinfunction "RC3_8") (pintype "bidirectional"))
    )
    (net (code "79") (name "/RC4") (class "Default")
      (node (ref "IC1") (pin "9") (pinfunction "RC4_9") (pintype "bidirectional"))
    )
    (net (code "80") (name "/RE9") (class "Default")
      (node (ref "IC1") (pin "19") (pinfunction "RE9_19") (pintype "bidirectional"))
    )
    (net (code "81") (name "/RG15") (class "Default")
      (node (ref "IC1") (pin "1") (pinfunction "RG15_1") (pintype "bidirectional"))
    )
    (net (code "82") (name "/SCK1") (class "Default")
      (node (ref "IC1") (pin "55") (pinfunction "RF6_55") (pintype "bidirectional"))
      (node (ref "V1") (pin "2") (pinfunction "A_2") (pintype "input"))
    )
    (net (code "83") (name "/SDI1") (class "Default")
      (node (ref "IC1") (pin "54") (pinfunction "RF7_54") (pintype "bidirectional"))
      (node (ref "V1") (pin "8") (pinfunction "Y_8") (pintype "tri_state"))
    )
    (net (code "84") (name "/SDO1") (class "Default")
      (node (ref "IC1") (pin "53") (pinfunction "RF8_53") (pintype "bidirectional"))
      (node (ref "V1") (pin "5") (pinfunction "A_5") (pintype "input"))
    )
    (net (code "85") (name "/TEMP_1") (class "Default")
      (node (ref "IC1") (pin "25") (pinfunction "RB0_25") (pintype "bidirectional"))
      (node (ref "J2") (pin "B4") (pinfunction "B4_B4") (pintype "passive"))
    )
    (net (code "86") (name "/TEMP_2") (class "Default")
      (node (ref "IC1") (pin "24") (pinfunction "RB1_24") (pintype "bidirectional"))
      (node (ref "J2") (pin "A4") (pinfunction "A4_A4") (pintype "passive"))
    )
    (net (code "87") (name "/TEMP_3") (class "Default")
      (node (ref "IC1") (pin "22") (pinfunction "RB3_22") (pintype "bidirectional"))
      (node (ref "J2") (pin "A3") (pinfunction "A3_A3") (pintype "passive"))
    )
    (net (code "88") (name "/TMS") (class "Default")
      (node (ref "IC1") (pin "17") (pinfunction "TMS_17") (pintype "input"))
    )
    (net (code "89") (name "/U1RX") (class "Default")
      (node (ref "IC1") (pin "52") (pinfunction "RF2_52") (pintype "bidirectional"))
      (node (ref "X2") (pin "4") (pinfunction "4_4") (pintype "passive"))
    )
    (net (code "90") (name "/U1TX") (class "Default")
      (node (ref "IC1") (pin "51") (pinfunction "RF3_51") (pintype "bidirectional"))
      (node (ref "X2") (pin "5") (pinfunction "5_5") (pintype "passive"))
    )
    (net (code "91") (name "/U2RX") (class "Default")
      (node (ref "IC1") (pin "49") (pinfunction "RF4_49") (pintype "bidirectional"))
      (node (ref "U$1") (pin "3") (pinfunction "TX0_3") (pintype "bidirectional"))
    )
    (net (code "92") (name "/U2TX") (class "Default")
      (node (ref "IC1") (pin "50") (pinfunction "RF5_50") (pintype "bidirectional"))
      (node (ref "U$1") (pin "4") (pinfunction "RX0_4") (pintype "bidirectional"))
    )
    (net (code "93") (name "/~{MCLR}") (class "Default")
      (node (ref "IC1") (pin "13") (pinfunction "~{MCLR}_13") (pintype "input"))
      (node (ref "JP2") (pin "1") (pinfunction "1_1") (pintype "passive"))
      (node (ref "R3") (pin "2") (pinfunction "2_2") (pintype "passive"))
    )
    (net (code "94") (name "/~{SS1_5V}") (class "Default")
      (node (ref "JP4") (pin "2") (pinfunction "2_2") (pintype "passive"))
      (node (ref "U1") (pin "2") (pinfunction "CS_2") (pintype "bidirectional"))
      (node (ref "V2") (pin "8") (pinfunction "Y_8") (pintype "tri_state"))
    )
    (net (code "95") (name "/~{SS1}") (class "Default")
      (node (ref "IC1") (pin "23") (pinfunction "RB2_23") (pintype "bidirectional"))
      (node (ref "V2") (pin "9") (pinfunction "A_9") (pintype "input"))
    )
    (net (code "96") (name "/~{SS2_5V}") (class "Default")
      (node (ref "JP6") (pin "2") (pinfunction "2_2") (pintype "passive"))
      (node (ref "U2") (pin "2") (pinfunction "CS_2") (pintype "bidirectional"))
      (node (ref "V2") (pin "11") (pinfunction "Y_11") (pintype "tri_state"))
    )
    (net (code "97") (name "/~{SS2}") (class "Default")
      (node (ref "IC1") (pin "14") (pinfunction "RG9_14") (pintype "bidirectional"))
      (node (ref "V2") (pin "12") (pinfunction "A_12") (pintype "input"))
    )
    (net (code "98") (name "Net-(IC1-VDDCORE)") (class "Default")
      (node (ref "C7") (pin "1") (pinfunction "1_1") (pintype "passive"))
      (node (ref "IC1") (pin "85") (pinfunction "VDDCORE_85") (pintype "power_in"))
    )
    (net (code "99") (name "Net-(U1-DIN)") (class "Default")
      (node (ref "R5") (pin "2") (pinfunction "2_2") (pintype "passive"))
      (node (ref "U1") (pin "10") (pinfunction "DIN_10") (pintype "bidirectional"))
    )
    (net (code "100") (name "Net-(U1-DOUT{slash}DRDY)") (class "Default")
      (node (ref "R6") (pin "2") (pinfunction "2_2") (pintype "passive"))
      (node (ref "U1") (pin "9") (pinfunction "DOUT/DRDY_9") (pintype "bidirectional"))
    )
    (net (code "101") (name "Net-(U1-SCLK)") (class "Default")
      (node (ref "R11") (pin "1") (pinfunction "1_1") (pintype "passive"))
      (node (ref "U1") (pin "1") (pinfunction "SCLK_1") (pintype "bidirectional"))
    )
    (net (code "102") (name "Net-(U2-DIN)") (class "Default")
      (node (ref "R12") (pin "2") (pinfunction "2_2") (pintype "passive"))
      (node (ref "U2") (pin "10") (pinfunction "DIN_10") (pintype "bidirectional"))
    )
    (net (code "103") (name "Net-(U2-DOUT{slash}DRDY)") (class "Default")
      (node (ref "R13") (pin "2") (pinfunction "2_2") (pintype "passive"))
      (node (ref "U2") (pin "9") (pinfunction "DOUT/DRDY_9") (pintype "bidirectional"))
    )
    (net (code "104") (name "Net-(U2-SCLK)") (class "Default")
      (node (ref "R14") (pin "1") (pinfunction "1_1") (pintype "passive"))
      (node (ref "U2") (pin "1") (pinfunction "SCLK_1") (pintype "bidirectional"))
    )
    (net (code "105") (name "unconnected-(IC1-RA2-Pad58)") (class "Default")
      (node (ref "IC1") (pin "58") (pinfunction "RA2_58") (pintype "bidirectional"))
    )
    (net (code "106") (name "unconnected-(IC1-RA3-Pad59)") (class "Default")
      (node (ref "IC1") (pin "59") (pinfunction "RA3_59") (pintype "bidirectional"))
    )
    (net (code "107") (name "unconnected-(IC1-RA6-Pad91)") (class "Default")
      (node (ref "IC1") (pin "91") (pinfunction "RA6_91") (pintype "bidirectional"))
    )
    (net (code "108") (name "unconnected-(IC1-RA7-Pad92)") (class "Default")
      (node (ref "IC1") (pin "92") (pinfunction "RA7_92") (pintype "bidirectional"))
    )
    (net (code "109") (name "unconnected-(IC1-RA9-Pad28)") (class "Default")
      (node (ref "IC1") (pin "28") (pinfunction "RA9_28") (pintype "bidirectional"))
    )
    (net (code "110") (name "unconnected-(IC1-RA10-Pad29)") (class "Default")
      (node (ref "IC1") (pin "29") (pinfunction "RA10_29") (pintype "bidirectional"))
    )
    (net (code "111") (name "unconnected-(IC1-RA14-Pad66)") (class "Default")
      (node (ref "IC1") (pin "66") (pinfunction "RA14_66") (pintype "bidirectional"))
    )
    (net (code "112") (name "unconnected-(IC1-RA15-Pad67)") (class "Default")
      (node (ref "IC1") (pin "67") (pinfunction "RA15_67") (pintype "bidirectional"))
    )
    (net (code "113") (name "unconnected-(IC1-RB14-Pad43)") (class "Default")
      (node (ref "IC1") (pin "43") (pinfunction "RB14_43") (pintype "bidirectional"))
    )
    (net (code "114") (name "unconnected-(IC1-RB15-Pad44)") (class "Default")
      (node (ref "IC1") (pin "44") (pinfunction "RB15_44") (pintype "bidirectional"))
    )
    (net (code "115") (name "unconnected-(IC1-RC13-Pad73)") (class "Default")
      (node (ref "IC1") (pin "73") (pinfunction "RC13_73") (pintype "bidirectional"))
    )
    (net (code "116") (name "unconnected-(IC1-RC14-Pad74)") (class "Default")
      (node (ref "IC1") (pin "74") (pinfunction "RC14_74") (pintype "bidirectional"))
    )
    (net (code "117") (name "unconnected-(IC1-RD10-Pad70)") (class "Default")
      (node (ref "IC1") (pin "70") (pinfunction "RD10_70") (pintype "bidirectional"))
    )
    (net (code "118") (name "unconnected-(IC1-RD11-Pad71)") (class "Default")
      (node (ref "IC1") (pin "71") (pinfunction "RD11_71") (pintype "bidirectional"))
    )
    (net (code "119") (name "unconnected-(IC1-RD12-Pad79)") (class "Default")
      (node (ref "IC1") (pin "79") (pinfunction "RD12_79") (pintype "bidirectional"))
    )
    (net (code "120") (name "unconnected-(IC1-RD13-Pad80)") (class "Default")
      (node (ref "IC1") (pin "80") (pinfunction "RD13_80") (pintype "bidirectional"))
    )
    (net (code "121") (name "unconnected-(IC1-RD15-Pad48)") (class "Default")
      (node (ref "IC1") (pin "48") (pinfunction "RD15_48") (pintype "bidirectional"))
    )
    (net (code "122") (name "unconnected-(IC1-RF0-Pad87)") (class "Default")
      (node (ref "IC1") (pin "87") (pinfunction "RF0_87") (pintype "bidirectional"))
    )
    (net (code "123") (name "unconnected-(IC1-RF1-Pad88)") (class "Default")
      (node (ref "IC1") (pin "88") (pinfunction "RF1_88") (pintype "bidirectional"))
    )
    (net (code "124") (name "unconnected-(IC1-RF12-Pad40)") (class "Default")
      (node (ref "IC1") (pin "40") (pinfunction "RF12_40") (pintype "bidirectional"))
    )
    (net (code "125") (name "unconnected-(IC1-RF13-Pad39)") (class "Default")
      (node (ref "IC1") (pin "39") (pinfunction "RF13_39") (pintype "bidirectional"))
    )
    (net (code "126") (name "unconnected-(IC1-RG0-Pad90)") (class "Default")
      (node (ref "IC1") (pin "90") (pinfunction "RG0_90") (pintype "bidirectional"))
    )
    (net (code "127") (name "unconnected-(IC1-RG1-Pad89)") (class "Default")
      (node (ref "IC1") (pin "89") (pinfunction "RG1_89") (pintype "bidirectional"))
    )
    (net (code "128") (name "unconnected-(IC1-RG12-Pad96)") (class "Default")
      (node (ref "IC1") (pin "96") (pinfunction "RG12_96") (pintype "bidirectional"))
    )
    (net (code "129") (name "unconnected-(IC1-RG13-Pad97)") (class "Default")
      (node (ref "IC1") (pin "97") (pinfunction "RG13_97") (pintype "bidirectional"))
    )
    (net (code "130") (name "unconnected-(IC1-RG14-Pad95)") (class "Default")
      (node (ref "IC1") (pin "95") (pinfunction "RG14_95") (pintype "bidirectional"))
    )
    (net (code "131") (name "unconnected-(IC1-TCK-Pad38)") (class "Default")
      (node (ref "IC1") (pin "38") (pinfunction "TCK_38") (pintype "input"))
    )
    (net (code "132") (name "unconnected-(IC1-TDI-Pad60)") (class "Default")
      (node (ref "IC1") (pin "60") (pinfunction "TDI_60") (pintype "input"))
    )
    (net (code "133") (name "unconnected-(IC1-TDO-Pad61)") (class "Default")
      (node (ref "IC1") (pin "61") (pinfunction "TDO_61") (pintype "output"))
    )
    (net (code "134") (name "unconnected-(J2-PadA1)") (class "Default")
      (node (ref "J2") (pin "A1") (pinfunction "A1_A1") (pintype "passive"))
    )
    (net (code "135") (name "unconnected-(J2-PadA2)") (class "Default")
      (node (ref "J2") (pin "A2") (pinfunction "A2_A2") (pintype "passive"))
    )
    (net (code "136") (name "unconnected-(J2-PadA10)") (class "Default")
      (node (ref "J2") (pin "A10") (pinfunction "A10_A10") (pintype "passive"))
    )
    (net (code "137") (name "unconnected-(J2-PadA15)") (class "Default")
      (node (ref "J2") (pin "A15") (pinfunction "A15_A15") (pintype "passive"))
    )
    (net (code "138") (name "unconnected-(J2-PadA16)") (class "Default")
      (node (ref "J2") (pin "A16") (pinfunction "A16_A16") (pintype "passive"))
    )
    (net (code "139") (name "unconnected-(J2-PadA17)") (class "Default")
      (node (ref "J2") (pin "A17") (pinfunction "A17_A17") (pintype "passive"))
    )
    (net (code "140") (name "unconnected-(J2-PadA18)") (class "Default")
      (node (ref "J2") (pin "A18") (pinfunction "A18_A18") (pintype "passive"))
    )
    (net (code "141") (name "unconnected-(J2-PadA19)") (class "Default")
      (node (ref "J2") (pin "A19") (pinfunction "A19_A19") (pintype "passive"))
    )
    (net (code "142") (name "unconnected-(J2-PadA20)") (class "Default")
      (node (ref "J2") (pin "A20") (pinfunction "A20_A20") (pintype "passive"))
    )
    (net (code "143") (name "unconnected-(J2-PadA21)") (class "Default")
      (node (ref "J2") (pin "A21") (pinfunction "A21_A21") (pintype "passive"))
    )
    (net (code "144") (name "unconnected-(J2-PadA22)") (class "Default")
      (node (ref "J2") (pin "A22") (pinfunction "A22_A22") (pintype "passive"))
    )
    (net (code "145") (name "unconnected-(J2-PadA23)") (class "Default")
      (node (ref "J2") (pin "A23") (pinfunction "A23_A23") (pintype "passive"))
    )
    (net (code "146") (name "unconnected-(J2-PadA24)") (class "Default")
      (node (ref "J2") (pin "A24") (pinfunction "A24_A24") (pintype "passive"))
    )
    (net (code "147") (name "unconnected-(J2-PadA25)") (class "Default")
      (node (ref "J2") (pin "A25") (pinfunction "A25_A25") (pintype "passive"))
    )
    (net (code "148") (name "unconnected-(J2-PadA26)") (class "Default")
      (node (ref "J2") (pin "A26") (pinfunction "A26_A26") (pintype "passive"))
    )
    (net (code "149") (name "unconnected-(J2-PadA27)") (class "Default")
      (node (ref "J2") (pin "A27") (pinfunction "A27_A27") (pintype "passive"))
    )
    (net (code "150") (name "unconnected-(J2-PadA28)") (class "Default")
      (node (ref "J2") (pin "A28") (pinfunction "A28_A28") (pintype "passive"))
    )
    (net (code "151") (name "unconnected-(J2-PadA29)") (class "Default")
      (node (ref "J2") (pin "A29") (pinfunction "A29_A29") (pintype "passive"))
    )
    (net (code "152") (name "unconnected-(J2-PadA30)") (class "Default")
      (node (ref "J2") (pin "A30") (pinfunction "A30_A30") (pintype "passive"))
    )
    (net (code "153") (name "unconnected-(J2-PadA31)") (class "Default")
      (node (ref "J2") (pin "A31") (pinfunction "A31_A31") (pintype "passive"))
    )
    (net (code "154") (name "unconnected-(J2-PadA32)") (class "Default")
      (node (ref "J2") (pin "A32") (pinfunction "A32_A32") (pintype "passive"))
    )
    (net (code "155") (name "unconnected-(J2-PadB10)") (class "Default")
      (node (ref "J2") (pin "B10") (pinfunction "B10_B10") (pintype "passive"))
    )
    (net (code "156") (name "unconnected-(J2-PadB15)") (class "Default")
      (node (ref "J2") (pin "B15") (pinfunction "B15_B15") (pintype "passive"))
    )
    (net (code "157") (name "unconnected-(J2-PadB16)") (class "Default")
      (node (ref "J2") (pin "B16") (pinfunction "B16_B16") (pintype "passive"))
    )
    (net (code "158") (name "unconnected-(J2-PadB17)") (class "Default")
      (node (ref "J2") (pin "B17") (pinfunction "B17_B17") (pintype "passive"))
    )
    (net (code "159") (name "unconnected-(J2-PadB18)") (class "Default")
      (node (ref "J2") (pin "B18") (pinfunction "B18_B18") (pintype "passive"))
    )
    (net (code "160") (name "unconnected-(J2-PadB19)") (class "Default")
      (node (ref "J2") (pin "B19") (pinfunction "B19_B19") (pintype "passive"))
    )
    (net (code "161") (name "unconnected-(J2-PadB20)") (class "Default")
      (node (ref "J2") (pin "B20") (pinfunction "B20_B20") (pintype "passive"))
    )
    (net (code "162") (name "unconnected-(J2-PadB21)") (class "Default")
      (node (ref "J2") (pin "B21") (pinfunction "B21_B21") (pintype "passive"))
    )
    (net (code "163") (name "unconnected-(J2-PadB22)") (class "Default")
      (node (ref "J2") (pin "B22") (pinfunction "B22_B22") (pintype "passive"))
    )
    (net (code "164") (name "unconnected-(J2-PadB23)") (class "Default")
      (node (ref "J2") (pin "B23") (pinfunction "B23_B23") (pintype "passive"))
    )
    (net (code "165") (name "unconnected-(J2-PadB24)") (class "Default")
      (node (ref "J2") (pin "B24") (pinfunction "B24_B24") (pintype "passive"))
    )
    (net (code "166") (name "unconnected-(J2-PadB25)") (class "Default")
      (node (ref "J2") (pin "B25") (pinfunction "B25_B25") (pintype "passive"))
    )
    (net (code "167") (name "unconnected-(J2-PadB26)") (class "Default")
      (node (ref "J2") (pin "B26") (pinfunction "B26_B26") (pintype "passive"))
    )
    (net (code "168") (name "unconnected-(J2-PadB27)") (class "Default")
      (node (ref "J2") (pin "B27") (pinfunction "B27_B27") (pintype "passive"))
    )
    (net (code "169") (name "unconnected-(J2-PadB28)") (class "Default")
      (node (ref "J2") (pin "B28") (pinfunction "B28_B28") (pintype "passive"))
    )
    (net (code "170") (name "unconnected-(J2-PadB29)") (class "Default")
      (node (ref "J2") (pin "B29") (pinfunction "B29_B29") (pintype "passive"))
    )
    (net (code "171") (name "unconnected-(J2-PadB30)") (class "Default")
      (node (ref "J2") (pin "B30") (pinfunction "B30_B30") (pintype "passive"))
    )
    (net (code "172") (name "unconnected-(J2-PadB31)") (class "Default")
      (node (ref "J2") (pin "B31") (pinfunction "B31_B31") (pintype "passive"))
    )
    (net (code "173") (name "unconnected-(J2-PadB32)") (class "Default")
      (node (ref "J2") (pin "B32") (pinfunction "B32_B32") (pintype "passive"))
    )
    (net (code "174") (name "unconnected-(J2-PadC10)") (class "Default")
      (node (ref "J2") (pin "C10") (pinfunction "C10_C10") (pintype "passive"))
    )
    (net (code "175") (name "unconnected-(J2-PadC15)") (class "Default")
      (node (ref "J2") (pin "C15") (pinfunction "C15_C15") (pintype "passive"))
    )
    (net (code "176") (name "unconnected-(J2-PadC16)") (class "Default")
      (node (ref "J2") (pin "C16") (pinfunction "C16_C16") (pintype "passive"))
    )
    (net (code "177") (name "unconnected-(J2-PadC17)") (class "Default")
      (node (ref "J2") (pin "C17") (pinfunction "C17_C17") (pintype "passive"))
    )
    (net (code "178") (name "unconnected-(J2-PadC18)") (class "Default")
      (node (ref "J2") (pin "C18") (pinfunction "C18_C18") (pintype "passive"))
    )
    (net (code "179") (name "unconnected-(J2-PadC19)") (class "Default")
      (node (ref "J2") (pin "C19") (pinfunction "C19_C19") (pintype "passive"))
    )
    (net (code "180") (name "unconnected-(J2-PadC20)") (class "Default")
      (node (ref "J2") (pin "C20") (pinfunction "C20_C20") (pintype "passive"))
    )
    (net (code "181") (name "unconnected-(J2-PadC21)") (class "Default")
      (node (ref "J2") (pin "C21") (pinfunction "C21_C21") (pintype "passive"))
    )
    (net (code "182") (name "unconnected-(J2-PadC22)") (class "Default")
      (node (ref "J2") (pin "C22") (pinfunction "C22_C22") (pintype "passive"))
    )
    (net (code "183") (name "unconnected-(J2-PadC23)") (class "Default")
      (node (ref "J2") (pin "C23") (pinfunction "C23_C23") (pintype "passive"))
    )
    (net (code "184") (name "unconnected-(J2-PadC24)") (class "Default")
      (node (ref "J2") (pin "C24") (pinfunction "C24_C24") (pintype "passive"))
    )
    (net (code "185") (name "unconnected-(J2-PadC25)") (class "Default")
      (node (ref "J2") (pin "C25") (pinfunction "C25_C25") (pintype "passive"))
    )
    (net (code "186") (name "unconnected-(J2-PadC26)") (class "Default")
      (node (ref "J2") (pin "C26") (pinfunction "C26_C26") (pintype "passive"))
    )
    (net (code "187") (name "unconnected-(J2-PadC27)") (class "Default")
      (node (ref "J2") (pin "C27") (pinfunction "C27_C27") (pintype "passive"))
    )
    (net (code "188") (name "unconnected-(J2-PadC28)") (class "Default")
      (node (ref "J2") (pin "C28") (pinfunction "C28_C28") (pintype "passive"))
    )
    (net (code "189") (name "unconnected-(J2-PadC29)") (class "Default")
      (node (ref "J2") (pin "C29") (pinfunction "C29_C29") (pintype "passive"))
    )
    (net (code "190") (name "unconnected-(J2-PadC30)") (class "Default")
      (node (ref "J2") (pin "C30") (pinfunction "C30_C30") (pintype "passive"))
    )
    (net (code "191") (name "unconnected-(J2-PadC31)") (class "Default")
      (node (ref "J2") (pin "C31") (pinfunction "C31_C31") (pintype "passive"))
    )
    (net (code "192") (name "unconnected-(J2-PadC32)") (class "Default")
      (node (ref "J2") (pin "C32") (pinfunction "C32_C32") (pintype "passive"))
    )
    (net (code "193") (name "unconnected-(JP1-Pad6)") (class "Default")
      (node (ref "JP1") (pin "6") (pinfunction "6_6") (pintype "passive"))
    )
    (net (code "194") (name "unconnected-(JP2-Pad6)") (class "Default")
      (node (ref "JP2") (pin "6") (pinfunction "6_6") (pintype "passive"))
    )
    (net (code "195") (name "unconnected-(PIC16-Pad2)") (class "Default")
      (node (ref "PIC16") (pin "2") (pinfunction "2_2") (pintype "passive"))
    )
    (net (code "196") (name "unconnected-(PIC16-Pad3)") (class "Default")
      (node (ref "PIC16") (pin "3") (pinfunction "3_3") (pintype "passive"))
    )
    (net (code "197") (name "unconnected-(PIC16-Pad13)") (class "Default")
      (node (ref "PIC16") (pin "13") (pinfunction "13_13") (pintype "passive"))
    )
    (net (code "198") (name "unconnected-(U$1-CLK-Pad6)") (class "Default")
      (node (ref "U$1") (pin "6") (pinfunction "CLK_6") (pintype "bidirectional"))
    )
    (net (code "199") (name "unconnected-(U$1-CS-Pad5)") (class "Default")
      (node (ref "U$1") (pin "5") (pinfunction "CS_5") (pintype "bidirectional"))
    )
    (net (code "200") (name "unconnected-(U$1-GND2-Pad15)") (class "Default")
      (node (ref "U$1") (pin "15") (pinfunction "GND2_15") (pintype "bidirectional"))
    )
    (net (code "201") (name "unconnected-(U$1-MISO-Pad7)") (class "Default")
      (node (ref "U$1") (pin "7") (pinfunction "MISO_7") (pintype "bidirectional"))
    )
    (net (code "202") (name "unconnected-(U$1-MOSI-Pad8)") (class "Default")
      (node (ref "U$1") (pin "8") (pinfunction "MOSI_8") (pintype "bidirectional"))
    )
    (net (code "203") (name "unconnected-(U$1-NAV-Pad14)") (class "Default")
      (node (ref "U$1") (pin "14") (pinfunction "NAV_14") (pintype "bidirectional"))
    )
    (net (code "204") (name "unconnected-(U$1-RX1-Pad12)") (class "Default")
      (node (ref "U$1") (pin "12") (pinfunction "RX1_12") (pintype "bidirectional"))
    )
    (net (code "205") (name "unconnected-(U$1-SCL-Pad10)") (class "Default")
      (node (ref "U$1") (pin "10") (pinfunction "SCL_10") (pintype "bidirectional"))
    )
    (net (code "206") (name "unconnected-(U$1-SDA-Pad9)") (class "Default")
      (node (ref "U$1") (pin "9") (pinfunction "SDA_9") (pintype "bidirectional"))
    )
    (net (code "207") (name "unconnected-(U$1-TX1-Pad11)") (class "Default")
      (node (ref "U$1") (pin "11") (pinfunction "TX1_11") (pintype "bidirectional"))
    )
    (net (code "208") (name "unconnected-(X1-Pad15)") (class "Default")
      (node (ref "X1") (pin "15") (pinfunction "15_15") (pintype "passive"))
    )
    (net (code "209") (name "unconnected-(X2-Pad3)") (class "Default")
      (node (ref "X2") (pin "3") (pinfunction "3_3") (pintype "passive"))
    )
    (net (code "210") (name "unconnected-(X2-Pad10)") (class "Default")
      (node (ref "X2") (pin "10") (pinfunction "10_10") (pintype "passive"))
    )
    (net (code "211") (name "unconnected-(X2-Pad11)") (class "Default")
      (node (ref "X2") (pin "11") (pinfunction "11_11") (pintype "passive"))
    )
  )
)
